# Explore_Labs_ESP8266_WiFi_Internet_of_Th.net
KiCad netlist of a schematic drawn in EAGLE
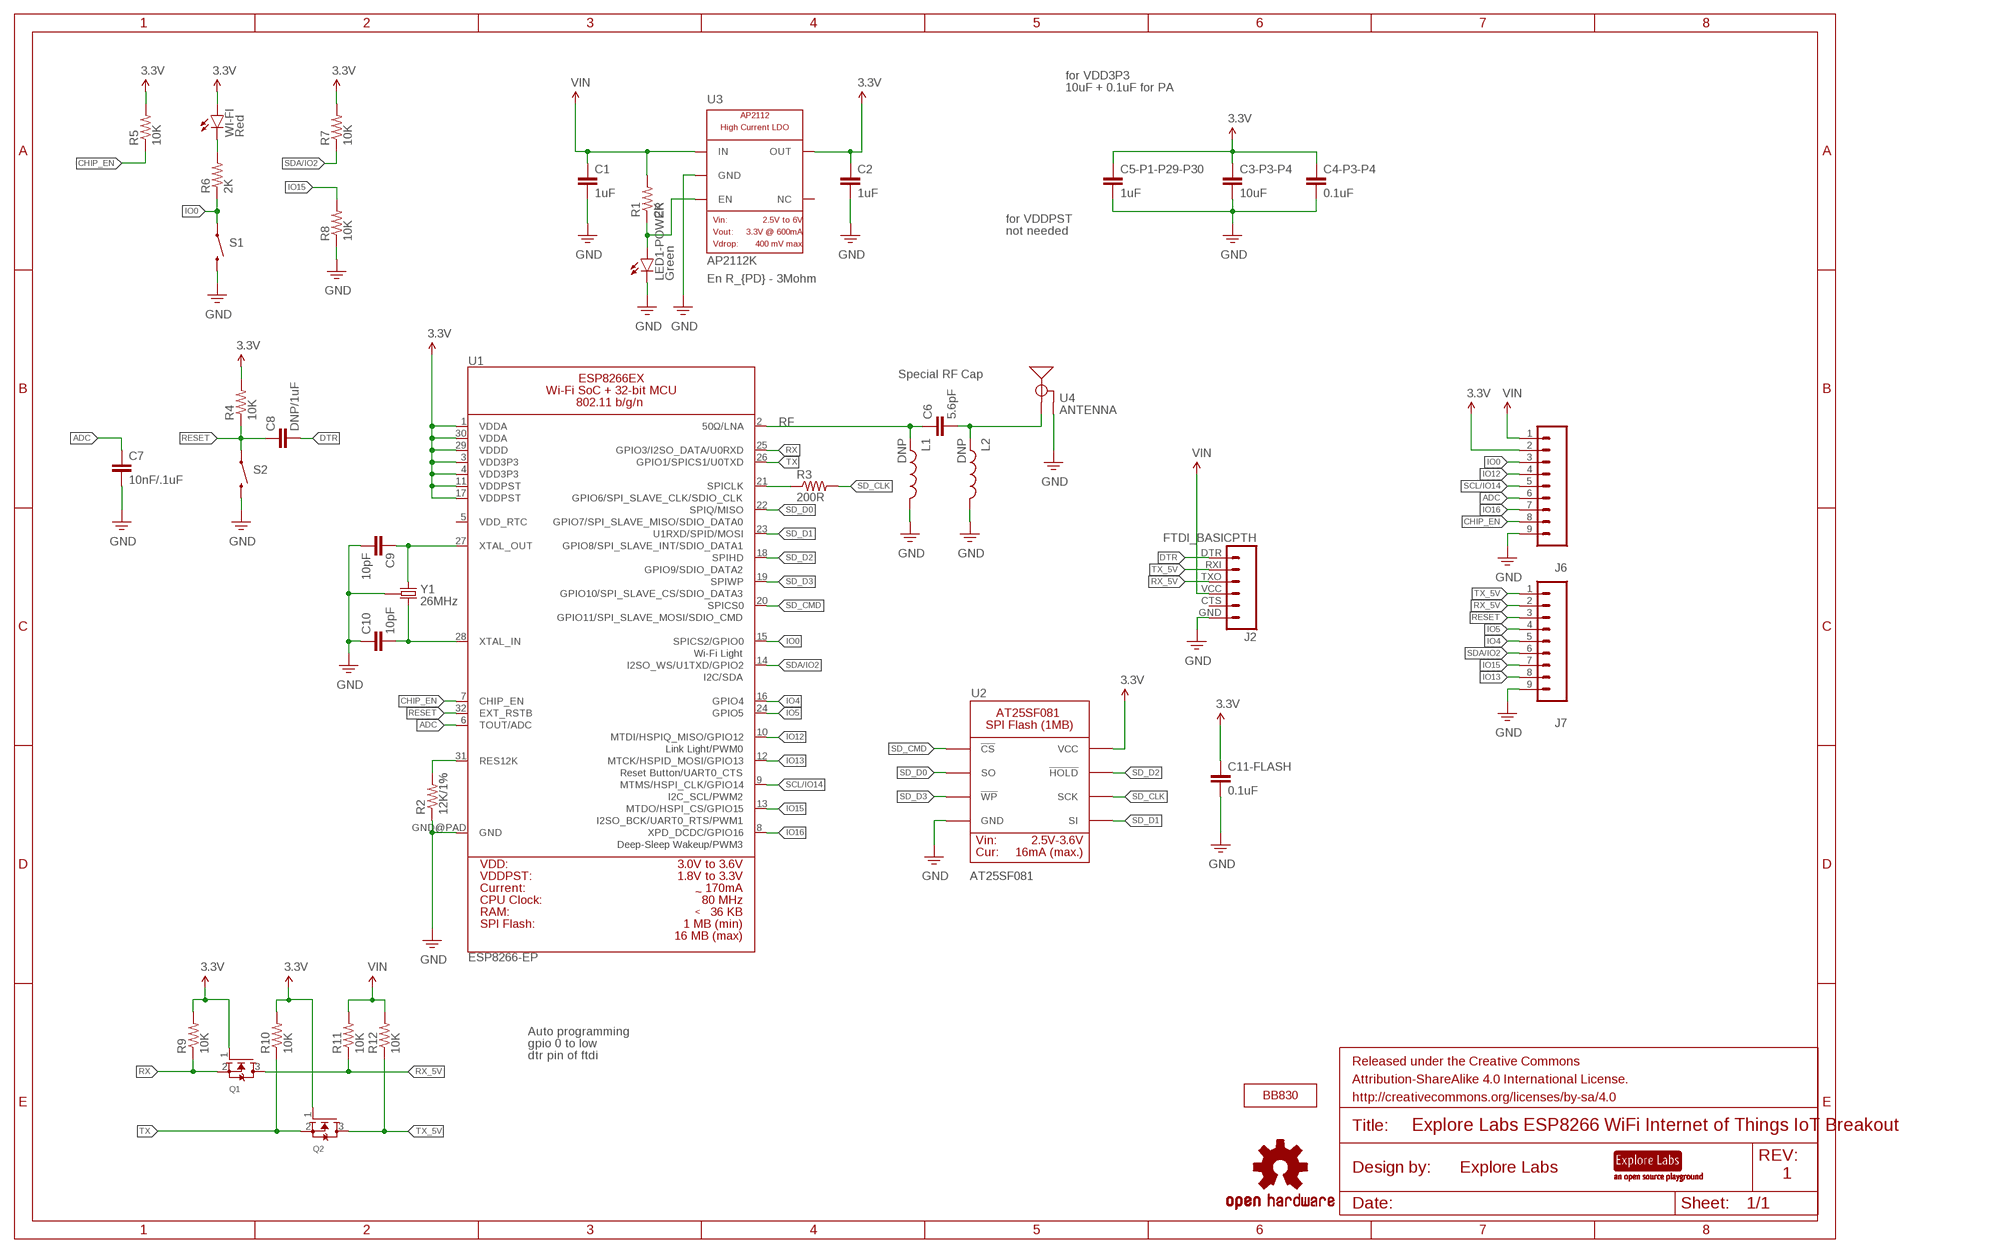
[diagram p0: schematic, sheet 1]

(export (version "E")
  (design (tool "Eeschema 10.0.6"))
  (components
    (comp (ref "C1")
      (value "1uF")
      (footprint "eagle-import:0402-CAP")
      (libsource (lib "eagle-import") (part "CAPACITOR-0402"))
    )
    (comp (ref "C2")
      (value "1uF")
      (footprint "eagle-import:0402-CAP")
      (libsource (lib "eagle-import") (part "CAPACITOR-0402"))
    )
    (comp (ref "C3-P3-P4")
      (value "10uF")
      (footprint "eagle-import:0603-CAP")
      (libsource (lib "eagle-import") (part "CAPACITOR"))
    )
    (comp (ref "C4-P3-P4")
      (value "0.1uF")
      (footprint "eagle-import:0402-CAP")
      (libsource (lib "eagle-import") (part "CAPACITOR-0402"))
    )
    (comp (ref "C5-P1-P29-P30")
      (value "1uF")
      (footprint "eagle-import:0402-CAP")
      (libsource (lib "eagle-import") (part "CAPACITOR-0402"))
    )
    (comp (ref "C6")
      (value "5.6pF")
      (footprint "eagle-import:0402-CAP")
      (libsource (lib "eagle-import") (part "CAPACITOR-0402"))
    )
    (comp (ref "C7")
      (value "10nF/.1uF")
      (footprint "eagle-import:0402-CAP")
      (libsource (lib "eagle-import") (part "CAPACITOR-0402"))
    )
    (comp (ref "C8")
      (value "DNP/1uF")
      (footprint "eagle-import:0402-CAP")
      (libsource (lib "eagle-import") (part "CAPACITOR-0402"))
    )
    (comp (ref "C9")
      (value "10pF")
      (footprint "eagle-import:0402-CAP")
      (libsource (lib "eagle-import") (part "CAPACITOR-0402"))
    )
    (comp (ref "C10")
      (value "10pF")
      (footprint "eagle-import:0402-CAP")
      (libsource (lib "eagle-import") (part "CAPACITOR-0402"))
    )
    (comp (ref "C11-FLASH")
      (value "0.1uF")
      (footprint "eagle-import:0402-CAP")
      (libsource (lib "eagle-import") (part "CAPACITOR-0402"))
    )
    (comp (ref "J2")
      (value "FTDI_BASICPTH")
      (footprint "eagle-import:FTDI_BASIC")
      (libsource (lib "eagle-import") (part "FTDI_BASICPTH"))
    )
    (comp (ref "J6")
      (value "M09")
      (footprint "eagle-import:1X09")
      (libsource (lib "eagle-import") (part "M09"))
    )
    (comp (ref "J7")
      (value "M09")
      (footprint "eagle-import:1X09")
      (libsource (lib "eagle-import") (part "M09"))
    )
    (comp (ref "L1")
      (value "DNP")
      (footprint "eagle-import:0402-FERRITE")
      (libsource (lib "eagle-import") (part "INDUCTOR"))
    )
    (comp (ref "L2")
      (value "DNP")
      (footprint "eagle-import:0402-FERRITE")
      (libsource (lib "eagle-import") (part "INDUCTOR"))
    )
    (comp (ref "LED1-POWER")
      (value "Green")
      (footprint "eagle-import:LED-0603")
      (libsource (lib "eagle-import") (part "LED0603"))
    )
    (comp (ref "LOGO1")
      (value "OSHW-LOGOBOTTOM")
      (footprint "eagle-import:OSHW-LOGO-M-BOTTOM")
      (libsource (lib "eagle-import") (part "OSHW-LOGOBOTTOM"))
    )
    (comp (ref "Q1")
      (value "MOSFET-N")
      (footprint "eagle-import:SOT23")
      (libsource (lib "eagle-import") (part "MOSFET-N"))
    )
    (comp (ref "Q2")
      (value "MOSFET-N")
      (footprint "eagle-import:SOT23")
      (libsource (lib "eagle-import") (part "MOSFET-N"))
    )
    (comp (ref "R1")
      (value "2K")
      (footprint "eagle-import:0402-RES")
      (libsource (lib "eagle-import") (part "RESISTOR-0402"))
    )
    (comp (ref "R2")
      (value "12K/1%")
      (footprint "eagle-import:0402-RES")
      (libsource (lib "eagle-import") (part "RESISTOR-0402"))
    )
    (comp (ref "R3")
      (value "200R")
      (footprint "eagle-import:0402-RES")
      (libsource (lib "eagle-import") (part "RESISTOR-0402"))
    )
    (comp (ref "R4")
      (value "10K")
      (footprint "eagle-import:0402-RES")
      (libsource (lib "eagle-import") (part "RESISTOR-0402"))
    )
    (comp (ref "R5")
      (value "10K")
      (footprint "eagle-import:0402-RES")
      (libsource (lib "eagle-import") (part "RESISTOR-0402"))
    )
    (comp (ref "R6")
      (value "2K")
      (footprint "eagle-import:0402-RES")
      (libsource (lib "eagle-import") (part "RESISTOR-0402"))
    )
    (comp (ref "R7")
      (value "10K")
      (footprint "eagle-import:0402-RES")
      (libsource (lib "eagle-import") (part "RESISTOR-0402"))
    )
    (comp (ref "R8")
      (value "10K")
      (footprint "eagle-import:0402-RES")
      (libsource (lib "eagle-import") (part "RESISTOR-0402"))
    )
    (comp (ref "R9")
      (value "10K")
      (footprint "eagle-import:0402-RES")
      (libsource (lib "eagle-import") (part "RESISTOR-0402"))
    )
    (comp (ref "R10")
      (value "10K")
      (footprint "eagle-import:0402-RES")
      (libsource (lib "eagle-import") (part "RESISTOR-0402"))
    )
    (comp (ref "R11")
      (value "10K")
      (footprint "eagle-import:0402-RES")
      (libsource (lib "eagle-import") (part "RESISTOR-0402"))
    )
    (comp (ref "R12")
      (value "10K")
      (footprint "eagle-import:0402-RES")
      (libsource (lib "eagle-import") (part "RESISTOR-0402"))
    )
    (comp (ref "S1")
      (value "SWITCH-NO-MOM")
      (footprint "eagle-import:KXT-SWITCH")
      (libsource (lib "eagle-import") (part "SWITCH-NO-MOM"))
    )
    (comp (ref "S2")
      (value "SWITCH-NO-MOM")
      (footprint "eagle-import:KXT-SWITCH")
      (libsource (lib "eagle-import") (part "SWITCH-NO-MOM"))
    )
    (comp (ref "U$3")
      (value "26MHz")
      (footprint "eagle-import:CRYSTAL-3225")
      (libsource (lib "eagle-import") (part "CRYSTAL-GROUNDED"))
    )
    (comp (ref "U$4")
      (value "EXPLORE-LABS-LOGOBOTTOM")
      (footprint "eagle-import:EXLABS_LOGO_0.25")
      (libsource (lib "eagle-import") (part "EXPLORE-LABS-LOGOBOTTOM"))
    )
    (comp (ref "U$7")
      (value "BREADBOARD-830")
      (footprint "eagle-import:BREADBOARD-830")
      (libsource (lib "eagle-import") (part "BREADBOARD-830"))
    )
    (comp (ref "U1")
      (value "ESP8266-EP")
      (footprint "eagle-import:QFN32")
      (libsource (lib "eagle-import") (part "ESP8266-EP"))
    )
    (comp (ref "U2")
      (value "AT25SF081")
      (footprint "eagle-import:SO08")
      (libsource (lib "eagle-import") (part "AT25SF081"))
    )
    (comp (ref "U3")
      (value "AP2112K")
      (footprint "eagle-import:SOT23-LDO")
      (libsource (lib "eagle-import") (part "AP2112K"))
    )
    (comp (ref "U4")
      (value "ANTENNA")
      (footprint "eagle-import:ANTENNA-WROOM-02-INV")
      (libsource (lib "eagle-import") (part "ANTENNA"))
    )
    (comp (ref "WI-FI")
      (value "Red")
      (footprint "eagle-import:LED-0603")
      (libsource (lib "eagle-import") (part "LED0603"))
    )
  )
  (nets
    (net (code "1") (name "/RF") (class "Default")
      (node (ref "C6") (pin "1") (pinfunction "1_1") (pintype "passive"))
      (node (ref "L1") (pin "1") (pinfunction "1_1") (pintype "passive"))
      (node (ref "U1") (pin "2") (pinfunction "50Ω/LNA_2") (pintype "bidirectional"))
    )
    (net (code "2") (name "3.3V") (class "Default")
      (node (ref "C11-FLASH") (pin "1") (pinfunction "1_1") (pintype "passive"))
      (node (ref "C2") (pin "1") (pinfunction "1_1") (pintype "passive"))
      (node (ref "C3-P3-P4") (pin "1") (pinfunction "1_1") (pintype "passive"))
      (node (ref "C4-P3-P4") (pin "1") (pinfunction "1_1") (pintype "passive"))
      (node (ref "C5-P1-P29-P30") (pin "1") (pinfunction "1_1") (pintype "passive"))
      (node (ref "J6") (pin "2") (pinfunction "2_2") (pintype "passive"))
      (node (ref "Q1") (pin "1") (pinfunction "G_1") (pintype "bidirectional"))
      (node (ref "Q2") (pin "1") (pinfunction "G_1") (pintype "bidirectional"))
      (node (ref "R10") (pin "2") (pinfunction "2_2") (pintype "passive"))
      (node (ref "R4") (pin "2") (pinfunction "2_2") (pintype "passive"))
      (node (ref "R5") (pin "2") (pinfunction "2_2") (pintype "passive"))
      (node (ref "R7") (pin "2") (pinfunction "2_2") (pintype "passive"))
      (node (ref "R9") (pin "2") (pinfunction "2_2") (pintype "passive"))
      (node (ref "U1") (pin "1") (pinfunction "VDDA_1") (pintype "power_in"))
      (node (ref "U1") (pin "11") (pinfunction "VDDPST_11") (pintype "power_in"))
      (node (ref "U1") (pin "17") (pinfunction "VDDPST_17") (pintype "power_in"))
      (node (ref "U1") (pin "29") (pinfunction "VDDD_29") (pintype "power_in"))
      (node (ref "U1") (pin "3") (pinfunction "VDD3P3_3") (pintype "power_in"))
      (node (ref "U1") (pin "30") (pinfunction "VDDA_30") (pintype "power_in"))
      (node (ref "U1") (pin "4") (pinfunction "VDD3P3_4") (pintype "power_in"))
      (node (ref "U2") (pin "8") (pinfunction "VCC_8") (pintype "bidirectional"))
      (node (ref "U3") (pin "5") (pinfunction "OUT_5") (pintype "power_in"))
      (node (ref "WI-FI") (pin "A") (pinfunction "A_A") (pintype "passive"))
    )
    (net (code "3") (name "ADC") (class "Default")
      (node (ref "C7") (pin "1") (pinfunction "1_1") (pintype "passive"))
      (node (ref "J6") (pin "6") (pinfunction "6_6") (pintype "passive"))
      (node (ref "U1") (pin "6") (pinfunction "TOUT/ADC_6") (pintype "input"))
    )
    (net (code "4") (name "CHIP_EN") (class "Default")
      (node (ref "J6") (pin "8") (pinfunction "8_8") (pintype "passive"))
      (node (ref "R5") (pin "1") (pinfunction "1_1") (pintype "passive"))
      (node (ref "U1") (pin "7") (pinfunction "CHIP_EN_7") (pintype "input"))
    )
    (net (code "5") (name "DTR") (class "Default")
      (node (ref "C8") (pin "2") (pinfunction "2_2") (pintype "passive"))
      (node (ref "J2") (pin "DTR") (pinfunction "1_DTR") (pintype "passive"))
    )
    (net (code "6") (name "GND") (class "Default")
      (node (ref "C1") (pin "2") (pinfunction "2_2") (pintype "passive"))
      (node (ref "C10") (pin "1") (pinfunction "1_1") (pintype "passive"))
      (node (ref "C11-FLASH") (pin "2") (pinfunction "2_2") (pintype "passive"))
      (node (ref "C2") (pin "2") (pinfunction "2_2") (pintype "passive"))
      (node (ref "C3-P3-P4") (pin "2") (pinfunction "2_2") (pintype "passive"))
      (node (ref "C4-P3-P4") (pin "2") (pinfunction "2_2") (pintype "passive"))
      (node (ref "C5-P1-P29-P30") (pin "2") (pinfunction "2_2") (pintype "passive"))
      (node (ref "C7") (pin "2") (pinfunction "2_2") (pintype "passive"))
      (node (ref "C9") (pin "2") (pinfunction "2_2") (pintype "passive"))
      (node (ref "J2") (pin "GND") (pinfunction "6_GND") (pintype "passive"))
      (node (ref "J6") (pin "9") (pinfunction "9_9") (pintype "passive"))
      (node (ref "J7") (pin "9") (pinfunction "9_9") (pintype "passive"))
      (node (ref "L1") (pin "2") (pinfunction "2_2") (pintype "passive"))
      (node (ref "L2") (pin "2") (pinfunction "2_2") (pintype "passive"))
      (node (ref "LED1-POWER") (pin "C") (pinfunction "C_C") (pintype "passive"))
      (node (ref "R2") (pin "1") (pinfunction "1_1") (pintype "passive"))
      (node (ref "R8") (pin "1") (pinfunction "1_1") (pintype "passive"))
      (node (ref "S1") (pin "2") (pinfunction "2_2") (pintype "passive"))
      (node (ref "S2") (pin "2") (pinfunction "2_2") (pintype "passive"))
      (node (ref "U$3") (pin "2") (pinfunction "3_2") (pintype "passive"))
      (node (ref "U$3") (pin "4") (pinfunction "3_4") (pintype "passive"))
      (node (ref "U1") (pin "GND@PAD") (pinfunction "GND_GND@PAD") (pintype "power_in"))
      (node (ref "U2") (pin "4") (pinfunction "GND_4") (pintype "bidirectional"))
      (node (ref "U3") (pin "2") (pinfunction "GND_2") (pintype "power_in"))
      (node (ref "U4") (pin "GND") (pinfunction "GND_GND") (pintype "bidirectional"))
    )
    (net (code "7") (name "IO0") (class "Default")
      (node (ref "J6") (pin "3") (pinfunction "3_3") (pintype "passive"))
      (node (ref "R6") (pin "1") (pinfunction "1_1") (pintype "passive"))
      (node (ref "S1") (pin "1") (pinfunction "1_1") (pintype "passive"))
      (node (ref "U1") (pin "15") (pinfunction "SPICS2/GPIO0_15") (pintype "bidirectional"))
    )
    (net (code "8") (name "IO4") (class "Default")
      (node (ref "J7") (pin "5") (pinfunction "5_5") (pintype "passive"))
      (node (ref "U1") (pin "16") (pinfunction "GPIO4_16") (pintype "bidirectional"))
    )
    (net (code "9") (name "IO5") (class "Default")
      (node (ref "J7") (pin "4") (pinfunction "4_4") (pintype "passive"))
      (node (ref "U1") (pin "24") (pinfunction "GPIO5_24") (pintype "bidirectional"))
    )
    (net (code "10") (name "IO12") (class "Default")
      (node (ref "J6") (pin "4") (pinfunction "4_4") (pintype "passive"))
      (node (ref "U1") (pin "10") (pinfunction "MTDI/HSPIQ_MISO/GPIO12_10") (pintype "bidirectional"))
    )
    (net (code "11") (name "IO13") (class "Default")
      (node (ref "J7") (pin "8") (pinfunction "8_8") (pintype "passive"))
      (node (ref "U1") (pin "12") (pinfunction "MTCK/HSPID_MOSI/GPIO13_12") (pintype "bidirectional"))
    )
    (net (code "12") (name "IO15") (class "Default")
      (node (ref "J7") (pin "7") (pinfunction "7_7") (pintype "passive"))
      (node (ref "R8") (pin "2") (pinfunction "2_2") (pintype "passive"))
      (node (ref "U1") (pin "13") (pinfunction "MTDO/HSPI_CS/GPIO15_13") (pintype "bidirectional"))
    )
    (net (code "13") (name "IO16") (class "Default")
      (node (ref "J6") (pin "7") (pinfunction "7_7") (pintype "passive"))
      (node (ref "U1") (pin "8") (pinfunction "XPD_DCDC/GPIO16_8") (pintype "bidirectional"))
    )
    (net (code "14") (name "Net-(R6-Pad2)") (class "Default")
      (node (ref "R6") (pin "2") (pinfunction "2_2") (pintype "passive"))
      (node (ref "WI-FI") (pin "C") (pinfunction "C_C") (pintype "passive"))
    )
    (net (code "15") (name "Net-(U$3-2)") (class "Default")
      (node (ref "C10") (pin "2") (pinfunction "2_2") (pintype "passive"))
      (node (ref "U$3") (pin "3") (pinfunction "2_3") (pintype "passive"))
      (node (ref "U1") (pin "28") (pinfunction "XTAL_IN_28") (pintype "bidirectional"))
    )
    (net (code "16") (name "Net-(U1-RES12K)") (class "Default")
      (node (ref "R2") (pin "2") (pinfunction "2_2") (pintype "passive"))
      (node (ref "U1") (pin "31") (pinfunction "RES12K_31") (pintype "input"))
    )
    (net (code "17") (name "Net-(U1-SPICLK)") (class "Default")
      (node (ref "R3") (pin "1") (pinfunction "1_1") (pintype "passive"))
      (node (ref "U1") (pin "21") (pinfunction "SPICLK_21") (pintype "bidirectional"))
    )
    (net (code "18") (name "Net-(U1-XTAL_OUT)") (class "Default")
      (node (ref "C9") (pin "1") (pinfunction "1_1") (pintype "passive"))
      (node (ref "U$3") (pin "1") (pinfunction "1_1") (pintype "passive"))
      (node (ref "U1") (pin "27") (pinfunction "XTAL_OUT_27") (pintype "bidirectional"))
    )
    (net (code "19") (name "Net-(U3-EN)") (class "Default")
      (node (ref "LED1-POWER") (pin "A") (pinfunction "A_A") (pintype "passive"))
      (node (ref "R1") (pin "1") (pinfunction "1_1") (pintype "passive"))
      (node (ref "U3") (pin "3") (pinfunction "EN_3") (pintype "input"))
    )
    (net (code "20") (name "Net-(U4-SIGNAL)") (class "Default")
      (node (ref "C6") (pin "2") (pinfunction "2_2") (pintype "passive"))
      (node (ref "L2") (pin "1") (pinfunction "1_1") (pintype "passive"))
      (node (ref "U4") (pin "SIG") (pinfunction "SIGNAL_SIG") (pintype "bidirectional"))
    )
    (net (code "21") (name "RESET") (class "Default")
      (node (ref "C8") (pin "1") (pinfunction "1_1") (pintype "passive"))
      (node (ref "J7") (pin "3") (pinfunction "3_3") (pintype "passive"))
      (node (ref "R4") (pin "1") (pinfunction "1_1") (pintype "passive"))
      (node (ref "S2") (pin "1") (pinfunction "1_1") (pintype "passive"))
      (node (ref "U1") (pin "32") (pinfunction "EXT_RSTB_32") (pintype "input"))
    )
    (net (code "22") (name "RX") (class "Default")
      (node (ref "Q1") (pin "2") (pinfunction "S_2") (pintype "bidirectional"))
      (node (ref "R9") (pin "1") (pinfunction "1_1") (pintype "passive"))
      (node (ref "U1") (pin "25") (pinfunction "GPIO3/I2SO_DATA/U0RXD_25") (pintype "bidirectional"))
    )
    (net (code "23") (name "RX_5V") (class "Default")
      (node (ref "J2") (pin "TXO") (pinfunction "3_TXO") (pintype "passive"))
      (node (ref "J7") (pin "2") (pinfunction "2_2") (pintype "passive"))
      (node (ref "Q1") (pin "3") (pinfunction "D_3") (pintype "bidirectional"))
      (node (ref "R11") (pin "1") (pinfunction "1_1") (pintype "passive"))
    )
    (net (code "24") (name "SCL{slash}IO14") (class "Default")
      (node (ref "J6") (pin "5") (pinfunction "5_5") (pintype "passive"))
      (node (ref "U1") (pin "9") (pinfunction "MTMS/HSPI_CLK/GPIO14_9") (pintype "bidirectional"))
    )
    (net (code "25") (name "SDA{slash}IO2") (class "Default")
      (node (ref "J7") (pin "6") (pinfunction "6_6") (pintype "passive"))
      (node (ref "R7") (pin "1") (pinfunction "1_1") (pintype "passive"))
      (node (ref "U1") (pin "14") (pinfunction "I2SO_WS/U1TXD/GPIO2_14") (pintype "bidirectional"))
    )
    (net (code "26") (name "SD_CLK") (class "Default")
      (node (ref "R3") (pin "2") (pinfunction "2_2") (pintype "passive"))
      (node (ref "U2") (pin "6") (pinfunction "SCK_6") (pintype "bidirectional"))
    )
    (net (code "27") (name "SD_CMD") (class "Default")
      (node (ref "U1") (pin "20") (pinfunction "SPICS0_20") (pintype "bidirectional"))
      (node (ref "U2") (pin "1") (pinfunction "~{CS}_1") (pintype "bidirectional"))
    )
    (net (code "28") (name "SD_D0") (class "Default")
      (node (ref "U1") (pin "22") (pinfunction "SPIQ/MISO_22") (pintype "bidirectional"))
      (node (ref "U2") (pin "2") (pinfunction "SO_2") (pintype "bidirectional"))
    )
    (net (code "29") (name "SD_D1") (class "Default")
      (node (ref "U1") (pin "23") (pinfunction "U1RXD/SPID/MOSI_23") (pintype "bidirectional"))
      (node (ref "U2") (pin "5") (pinfunction "SI_5") (pintype "bidirectional"))
    )
    (net (code "30") (name "SD_D2") (class "Default")
      (node (ref "U1") (pin "18") (pinfunction "SPIHD_18") (pintype "bidirectional"))
      (node (ref "U2") (pin "7") (pinfunction "~{HOLD}_7") (pintype "bidirectional"))
    )
    (net (code "31") (name "SD_D3") (class "Default")
      (node (ref "U1") (pin "19") (pinfunction "SPIWP_19") (pintype "bidirectional"))
      (node (ref "U2") (pin "3") (pinfunction "~{WP}_3") (pintype "bidirectional"))
    )
    (net (code "32") (name "TX") (class "Default")
      (node (ref "Q2") (pin "2") (pinfunction "S_2") (pintype "bidirectional"))
      (node (ref "R10") (pin "1") (pinfunction "1_1") (pintype "passive"))
      (node (ref "U1") (pin "26") (pinfunction "GPIO1/SPICS1/U0TXD_26") (pintype "bidirectional"))
    )
    (net (code "33") (name "TX_5V") (class "Default")
      (node (ref "J2") (pin "RXI") (pinfunction "2_RXI") (pintype "passive"))
      (node (ref "J7") (pin "1") (pinfunction "1_1") (pintype "passive"))
      (node (ref "Q2") (pin "3") (pinfunction "D_3") (pintype "bidirectional"))
      (node (ref "R12") (pin "1") (pinfunction "1_1") (pintype "passive"))
    )
    (net (code "34") (name "VIN") (class "Default")
      (node (ref "C1") (pin "1") (pinfunction "1_1") (pintype "passive"))
      (node (ref "J2") (pin "VCC") (pinfunction "4_VCC") (pintype "passive"))
      (node (ref "J6") (pin "1") (pinfunction "1_1") (pintype "passive"))
      (node (ref "R1") (pin "2") (pinfunction "2_2") (pintype "passive"))
      (node (ref "R11") (pin "2") (pinfunction "2_2") (pintype "passive"))
      (node (ref "R12") (pin "2") (pinfunction "2_2") (pintype "passive"))
      (node (ref "U3") (pin "1") (pinfunction "IN_1") (pintype "power_in"))
    )
    (net (code "35") (name "unconnected-(J2-5-PadCTS)") (class "Default")
      (node (ref "J2") (pin "CTS") (pinfunction "5_CTS") (pintype "passive"))
    )
    (net (code "36") (name "unconnected-(U1-VDD_RTC-Pad5)") (class "Default")
      (node (ref "U1") (pin "5") (pinfunction "VDD_RTC_5") (pintype "no_connect"))
    )
    (net (code "37") (name "unconnected-(U3-NC-Pad4)") (class "Default")
      (node (ref "U3") (pin "4") (pinfunction "NC_4") (pintype "no_connect"))
    )
  )
)
